# AFE.net
KiCad netlist of a schematic drawn in Altium Designer
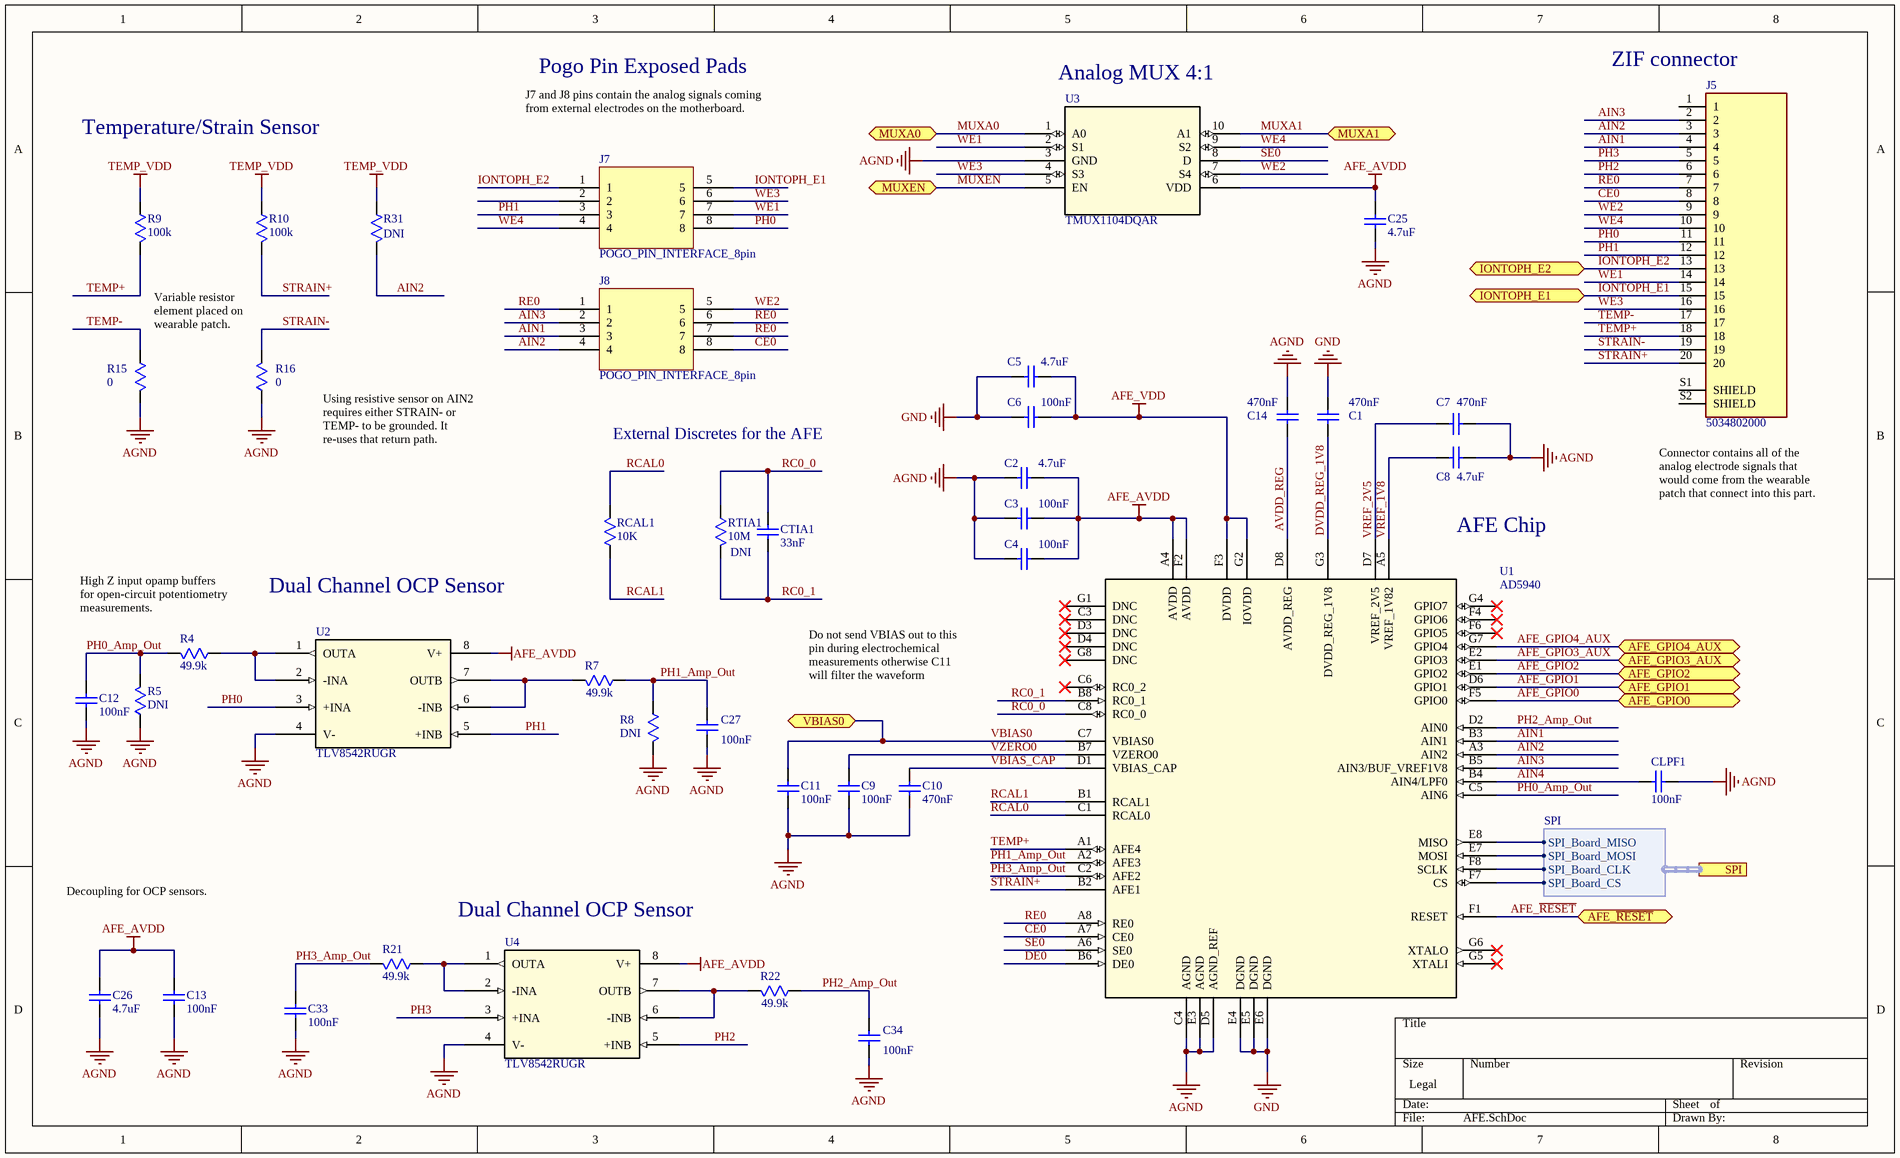
[diagram p0: AFE.SchDoc]

(export (version "E")
  (design (tool "Eeschema 10.0.6"))
  (components
    (comp (ref "C1")
      (value "470nF")
      (footprint "0201 cap")
      (description "Multilayer Chip Capacitor")
      (fields (field (name "Comment") "CAP") (field (name "DESIGNER") "OMIGA"))
      (libsource (lib "Schlib") (part "CAP SMD"))
    )
    (comp (ref "C2")
      (value "4.7uF")
      (footprint "0201 cap")
      (description "Multilayer Chip Capacitor")
      (fields (field (name "Comment") "CAP") (field (name "DESIGNER") "OMIGA"))
      (libsource (lib "Schlib") (part "CAP SMD"))
    )
    (comp (ref "C3")
      (value "100nF")
      (footprint "0201 cap")
      (description "Multilayer Chip Capacitor")
      (fields (field (name "Comment") "CAP") (field (name "DESIGNER") "OMIGA"))
      (libsource (lib "Schlib") (part "CAP SMD"))
    )
    (comp (ref "C4")
      (value "100nF")
      (footprint "0201 cap")
      (description "Multilayer Chip Capacitor")
      (fields (field (name "Comment") "CAP") (field (name "DESIGNER") "OMIGA"))
      (libsource (lib "Schlib") (part "CAP SMD"))
    )
    (comp (ref "C5")
      (value "4.7uF")
      (footprint "0201 cap")
      (description "Multilayer Chip Capacitor")
      (fields (field (name "Comment") "CAP") (field (name "DESIGNER") "OMIGA"))
      (libsource (lib "Schlib") (part "CAP SMD"))
    )
    (comp (ref "C6")
      (value "100nF")
      (footprint "0201 cap")
      (description "Multilayer Chip Capacitor")
      (fields (field (name "Comment") "CAP") (field (name "DESIGNER") "OMIGA"))
      (libsource (lib "Schlib") (part "CAP SMD"))
    )
    (comp (ref "C7")
      (value "470nF")
      (footprint "0201 cap")
      (description "Multilayer Chip Capacitor")
      (fields (field (name "Comment") "CAP") (field (name "DESIGNER") "OMIGA"))
      (libsource (lib "Schlib") (part "CAP SMD"))
    )
    (comp (ref "C8")
      (value "4.7uF")
      (footprint "0201 cap")
      (description "Multilayer Chip Capacitor")
      (fields (field (name "Comment") "CAP") (field (name "DESIGNER") "OMIGA"))
      (libsource (lib "Schlib") (part "CAP SMD"))
    )
    (comp (ref "C9")
      (value "100nF")
      (footprint "0402-CAP")
      (description "Multilayer Chip Capacitor")
      (fields (field (name "Comment") "CAP") (field (name "DESIGNER") "OMIGA"))
      (libsource (lib "Schlib") (part "CAP SMD"))
    )
    (comp (ref "C10")
      (value "470nF")
      (footprint "0201 cap")
      (description "Multilayer Chip Capacitor")
      (fields (field (name "Comment") "CAP") (field (name "DESIGNER") "OMIGA"))
      (libsource (lib "Schlib") (part "CAP SMD"))
    )
    (comp (ref "C11")
      (value "100nF")
      (footprint "0402-CAP")
      (description "Multilayer Chip Capacitor")
      (fields (field (name "Comment") "CAP") (field (name "DESIGNER") "OMIGA"))
      (libsource (lib "Schlib") (part "CAP SMD"))
    )
    (comp (ref "C12")
      (value "100nF")
      (footprint "0201 cap")
      (description "Multilayer Chip Capacitor")
      (fields (field (name "Comment") "CAP") (field (name "DESIGNER") "OMIGA"))
      (libsource (lib "Schlib") (part "CAP SMD"))
    )
    (comp (ref "C13")
      (value "100nF")
      (footprint "0201 cap")
      (description "Multilayer Chip Capacitor")
      (fields (field (name "Comment") "CAP") (field (name "DESIGNER") "OMIGA"))
      (libsource (lib "Schlib") (part "CAP SMD"))
    )
    (comp (ref "C14")
      (value "470nF")
      (footprint "0201 cap")
      (description "Multilayer Chip Capacitor")
      (fields (field (name "Comment") "CAP") (field (name "DESIGNER") "OMIGA"))
      (libsource (lib "Schlib") (part "CAP SMD"))
    )
    (comp (ref "C25")
      (value "4.7uF")
      (footprint "0201 cap")
      (description "Multilayer Chip Capacitor")
      (fields (field (name "Comment") "CAP") (field (name "DESIGNER") "OMIGA"))
      (libsource (lib "Schlib") (part "CAP SMD"))
    )
    (comp (ref "C26")
      (value "4.7uF")
      (footprint "0201 cap")
      (description "Multilayer Chip Capacitor")
      (fields (field (name "Comment") "CAP") (field (name "DESIGNER") "OMIGA"))
      (libsource (lib "Schlib") (part "CAP SMD"))
    )
    (comp (ref "C27")
      (value "100nF")
      (footprint "0201 cap")
      (description "Multilayer Chip Capacitor")
      (fields (field (name "Comment") "CAP") (field (name "DESIGNER") "OMIGA"))
      (libsource (lib "Schlib") (part "CAP SMD"))
    )
    (comp (ref "C33")
      (value "100nF")
      (footprint "0201 cap")
      (description "Multilayer Chip Capacitor")
      (fields (field (name "Comment") "CAP") (field (name "DESIGNER") "OMIGA"))
      (libsource (lib "Schlib") (part "CAP SMD"))
    )
    (comp (ref "C34")
      (value "100nF")
      (footprint "0201 cap")
      (description "Multilayer Chip Capacitor")
      (fields (field (name "Comment") "CAP") (field (name "DESIGNER") "OMIGA"))
      (libsource (lib "Schlib") (part "CAP SMD"))
    )
    (comp (ref "CLPF1")
      (value "100nF")
      (footprint "0201 cap")
      (description "Multilayer Chip Capacitor")
      (fields (field (name "Comment") "CAP") (field (name "DESIGNER") "OMIGA"))
      (libsource (lib "Schlib") (part "CAP SMD"))
    )
    (comp (ref "CTIA1")
      (value "33nF")
      (footprint "0402-CAP")
      (description "Multilayer Chip Capacitor")
      (fields (field (name "Comment") "CAP") (field (name "DESIGNER") "OMIGA"))
      (libsource (lib "Schlib") (part "CAP SMD"))
    )
    (comp (ref "J5")
      (value "5034802000")
      (footprint "MOLEX_5034802000")
      (description "20 Position FFC, FPC Connector Contacts, Top and Bottom 0.020 (0.50mm) Surface Mount, Right Angle")
      (fields (field (name "MP") "503480-2000") (field (name "MF") "Molex"))
      (libsource (lib "Schlib") (part "5034802000"))
    )
    (comp (ref "J7")
      (value "POGO_PIN_INTERFACE_8pin")
      (footprint "POGO_PIN_INTERFACE_8pin")
      (libsource (lib "Schlib") (part "POGO_PIN_INTERFACE_8pin"))
    )
    (comp (ref "J8")
      (value "POGO_PIN_INTERFACE_8pin")
      (footprint "POGO_PIN_INTERFACE_8pin")
      (libsource (lib "Schlib") (part "POGO_PIN_INTERFACE_8pin"))
    )
    (comp (ref "R4")
      (value "49.9k")
      (footprint "0201 res")
      (description "Surface Mount Resistor")
      (fields (field (name "Comment") "RES") (field (name "DESIGNER") "OMIGA"))
      (libsource (lib "Schlib") (part "RES SMD"))
    )
    (comp (ref "R5")
      (value "RES")
      (footprint "0201 res")
      (description "Surface Mount Resistor")
      (fields (field (name "DO NOT INSTALL") "DNI") (field (name "DESIGNER") "OMIGA"))
      (libsource (lib "Schlib") (part "RES SMD"))
    )
    (comp (ref "R7")
      (value "49.9k")
      (footprint "0201 res")
      (description "Surface Mount Resistor")
      (fields (field (name "Comment") "RES") (field (name "DESIGNER") "OMIGA"))
      (libsource (lib "Schlib") (part "RES SMD"))
    )
    (comp (ref "R8")
      (value "RES")
      (footprint "0201 res")
      (description "Surface Mount Resistor")
      (fields (field (name "DO NOT INSTALL") "DNI") (field (name "DESIGNER") "OMIGA"))
      (libsource (lib "Schlib") (part "RES SMD"))
    )
    (comp (ref "R9")
      (value "100k")
      (footprint "0201 res")
      (description "Surface Mount Resistor")
      (fields (field (name "Comment") "RES") (field (name "DESIGNER") "OMIGA"))
      (libsource (lib "Schlib") (part "RES SMD"))
    )
    (comp (ref "R10")
      (value "100k")
      (footprint "0201 res")
      (description "Surface Mount Resistor")
      (fields (field (name "Comment") "RES") (field (name "DESIGNER") "OMIGA"))
      (libsource (lib "Schlib") (part "RES SMD"))
    )
    (comp (ref "R15")
      (value "0")
      (footprint "0201 res")
      (description "Surface Mount Resistor")
      (fields (field (name "Comment") "RES") (field (name "DESIGNER") "OMIGA"))
      (libsource (lib "Schlib") (part "RES SMD"))
    )
    (comp (ref "R16")
      (value "0")
      (footprint "0201 res")
      (description "Surface Mount Resistor")
      (fields (field (name "Comment") "RES") (field (name "DESIGNER") "OMIGA"))
      (libsource (lib "Schlib") (part "RES SMD"))
    )
    (comp (ref "R21")
      (value "49.9k")
      (footprint "0201 res")
      (description "Surface Mount Resistor")
      (fields (field (name "Comment") "RES") (field (name "DESIGNER") "OMIGA"))
      (libsource (lib "Schlib") (part "RES SMD"))
    )
    (comp (ref "R22")
      (value "49.9k")
      (footprint "0201 res")
      (description "Surface Mount Resistor")
      (fields (field (name "Comment") "RES") (field (name "DESIGNER") "OMIGA"))
      (libsource (lib "Schlib") (part "RES SMD"))
    )
    (comp (ref "R31")
      (value "RES")
      (footprint "0201 res")
      (description "Surface Mount Resistor")
      (fields (field (name "DO NOT INSTALL") "DNI") (field (name "DESIGNER") "OMIGA"))
      (libsource (lib "Schlib") (part "RES SMD"))
    )
    (comp (ref "RCAL1")
      (value "10K")
      (footprint "0201 res")
      (description "Surface Mount Resistor")
      (fields (field (name "Comment") "RES") (field (name "DESIGNER") "OMIGA"))
      (libsource (lib "Schlib") (part "RES 0201"))
    )
    (comp (ref "RTIA1")
      (value "10M")
      (footprint "0402-RES")
      (description "Surface Mount Resistor")
      (fields
        (field (name "DO NOT INSTALL") "DNI")
        (field (name "Comment") "RES")
        (field (name "DESIGNER") "OMIGA")
      )
      (libsource (lib "Schlib") (part "RES SMD"))
    )
    (comp (ref "U1")
      (value "AD5940")
      (footprint "CB-56-3_ADI")
      (description "High Precision, Impedance, and\r\nElectrochemical Front End")
      (libsource (lib "Schlib") (part "AD5940"))
    )
    (comp (ref "U2")
      (value "TLV8542RUGR")
      (footprint "QFN50P150X150X40-8N")
      (description "Low power, tiny, low input bias current opamp")
      (libsource (lib "Schlib") (part "TLV8542RUGR"))
    )
    (comp (ref "U3")
      (value "TMUX1104DQAR")
      (footprint "USON_104DQAR_TEX")
      (description "No Description Available")
      (fields (field (name "COPYRIGHT") "Copyright (C) 2022 Ultra Librarian. All rights reserved."))
      (libsource (lib "Schlib") (part "TMUX1104DQAR_1"))
    )
    (comp (ref "U4")
      (value "TLV8542RUGR")
      (footprint "QFN50P150X150X40-8N")
      (description "Low power, tiny, low input bias current opamp")
      (libsource (lib "Schlib") (part "TLV8542RUGR"))
    )
  )
  (nets
    (net (code "2") (name "/AFE_GPIO0") (class "Default")
      (node (ref "U1") (pin "F5") (pinfunction "GPIO0_F5") (pintype "bidirectional"))
    )
    (net (code "3") (name "/AFE_GPIO1") (class "Default")
      (node (ref "U1") (pin "D6") (pinfunction "GPIO1_D6") (pintype "bidirectional"))
    )
    (net (code "4") (name "/AFE_GPIO2") (class "Default")
      (node (ref "U1") (pin "E1") (pinfunction "GPIO2_E1") (pintype "bidirectional"))
    )
    (net (code "5") (name "/AFE_GPIO3_AUX") (class "Default")
      (node (ref "U1") (pin "E2") (pinfunction "GPIO3_E2") (pintype "bidirectional"))
    )
    (net (code "6") (name "/AFE_GPIO4_AUX") (class "Default")
      (node (ref "U1") (pin "G7") (pinfunction "GPIO4_G7") (pintype "bidirectional"))
    )
    (net (code "7") (name "/AFE_~{RESET}") (class "Default")
      (node (ref "U1") (pin "F1") (pinfunction "RESET_F1") (pintype "input"))
    )
    (net (code "8") (name "/AIN1") (class "Default")
      (node (ref "J5") (pin "4") (pinfunction "4_4") (pintype "passive"))
      (node (ref "J8") (pin "3") (pinfunction "3_3") (pintype "passive"))
      (node (ref "U1") (pin "B3") (pinfunction "AIN1_B3") (pintype "input"))
    )
    (net (code "9") (name "/AIN2") (class "Default")
      (node (ref "J5") (pin "3") (pinfunction "3_3") (pintype "passive"))
      (node (ref "J8") (pin "4") (pinfunction "4_4") (pintype "passive"))
      (node (ref "R31") (pin "2") (pinfunction "2_2") (pintype "passive"))
      (node (ref "U1") (pin "A3") (pinfunction "AIN2_A3") (pintype "input"))
    )
    (net (code "10") (name "/AIN3") (class "Default")
      (node (ref "J5") (pin "2") (pinfunction "2_2") (pintype "passive"))
      (node (ref "J8") (pin "2") (pinfunction "2_2") (pintype "passive"))
      (node (ref "U1") (pin "B5") (pinfunction "AIN3/BUF_VREF1V8_B5") (pintype "input"))
    )
    (net (code "11") (name "/AIN4") (class "Default")
      (node (ref "CLPF1") (pin "1") (pinfunction "1_1") (pintype "passive"))
      (node (ref "U1") (pin "B4") (pinfunction "AIN4/LPF0_B4") (pintype "input"))
    )
    (net (code "12") (name "/AVDD_REG") (class "Default")
      (node (ref "C14") (pin "2") (pinfunction "2_2") (pintype "passive"))
      (node (ref "U1") (pin "D8") (pinfunction "AVDD_REG_D8") (pintype "power_in"))
    )
    (net (code "13") (name "/CE0") (class "Default")
      (node (ref "J5") (pin "8") (pinfunction "8_8") (pintype "passive"))
      (node (ref "J8") (pin "8") (pinfunction "8_8") (pintype "passive"))
      (node (ref "U1") (pin "A7") (pinfunction "CE0_A7") (pintype "input"))
    )
    (net (code "14") (name "/DE0") (class "Default")
      (node (ref "U1") (pin "B6") (pinfunction "DE0_B6") (pintype "input"))
    )
    (net (code "15") (name "/DVDD_REG_1V8") (class "Default")
      (node (ref "C1") (pin "2") (pinfunction "2_2") (pintype "passive"))
      (node (ref "U1") (pin "G3") (pinfunction "DVDD_REG_1V8_G3") (pintype "power_in"))
    )
    (net (code "16") (name "/IONTOPH_E1") (class "Default")
      (node (ref "J5") (pin "15") (pinfunction "15_15") (pintype "passive"))
      (node (ref "J7") (pin "5") (pinfunction "5_5") (pintype "passive"))
    )
    (net (code "17") (name "/IONTOPH_E2") (class "Default")
      (node (ref "J5") (pin "13") (pinfunction "13_13") (pintype "passive"))
      (node (ref "J7") (pin "1") (pinfunction "1_1") (pintype "passive"))
    )
    (net (code "18") (name "/MUXA0") (class "Default")
      (node (ref "U3") (pin "1") (pinfunction "A0_1") (pintype "bidirectional"))
    )
    (net (code "19") (name "/MUXA1") (class "Default")
      (node (ref "U3") (pin "10") (pinfunction "A1_10") (pintype "bidirectional"))
    )
    (net (code "20") (name "/MUXEN") (class "Default")
      (node (ref "U3") (pin "5") (pinfunction "EN_5") (pintype "passive"))
    )
    (net (code "21") (name "/PH0") (class "Default")
      (node (ref "J5") (pin "11") (pinfunction "11_11") (pintype "passive"))
      (node (ref "J7") (pin "8") (pinfunction "8_8") (pintype "passive"))
      (node (ref "U2") (pin "3") (pinfunction "+INA_3") (pintype "input"))
    )
    (net (code "22") (name "/PH0_Amp_Out") (class "Default")
      (node (ref "C12") (pin "1") (pinfunction "1_1") (pintype "passive"))
      (node (ref "R4") (pin "1") (pinfunction "1_1") (pintype "passive"))
      (node (ref "R5") (pin "1") (pinfunction "1_1") (pintype "passive"))
      (node (ref "U1") (pin "C5") (pinfunction "AIN6_C5") (pintype "input"))
    )
    (net (code "23") (name "/PH1") (class "Default")
      (node (ref "J5") (pin "12") (pinfunction "12_12") (pintype "passive"))
      (node (ref "J7") (pin "3") (pinfunction "3_3") (pintype "passive"))
      (node (ref "U2") (pin "5") (pinfunction "+INB_5") (pintype "input"))
    )
    (net (code "24") (name "/PH1_Amp_Out") (class "Default")
      (node (ref "C27") (pin "1") (pinfunction "1_1") (pintype "passive"))
      (node (ref "R7") (pin "1") (pinfunction "1_1") (pintype "passive"))
      (node (ref "R8") (pin "1") (pinfunction "1_1") (pintype "passive"))
      (node (ref "U1") (pin "A2") (pinfunction "AFE3_A2") (pintype "bidirectional"))
    )
    (net (code "25") (name "/PH2") (class "Default")
      (node (ref "J5") (pin "6") (pinfunction "6_6") (pintype "passive"))
      (node (ref "U4") (pin "5") (pinfunction "+INB_5") (pintype "input"))
    )
    (net (code "26") (name "/PH2_Amp_Out") (class "Default")
      (node (ref "C34") (pin "1") (pinfunction "1_1") (pintype "passive"))
      (node (ref "R22") (pin "1") (pinfunction "1_1") (pintype "passive"))
      (node (ref "U1") (pin "D2") (pinfunction "AIN0_D2") (pintype "input"))
    )
    (net (code "27") (name "/PH3") (class "Default")
      (node (ref "J5") (pin "5") (pinfunction "5_5") (pintype "passive"))
      (node (ref "U4") (pin "3") (pinfunction "+INA_3") (pintype "input"))
    )
    (net (code "28") (name "/PH3_Amp_Out") (class "Default")
      (node (ref "C33") (pin "1") (pinfunction "1_1") (pintype "passive"))
      (node (ref "R21") (pin "1") (pinfunction "1_1") (pintype "passive"))
      (node (ref "U1") (pin "C2") (pinfunction "AFE2_C2") (pintype "bidirectional"))
    )
    (net (code "29") (name "/RC0_0") (class "Default")
      (node (ref "CTIA1") (pin "1") (pinfunction "1_1") (pintype "passive"))
      (node (ref "RTIA1") (pin "1") (pinfunction "1_1") (pintype "passive"))
      (node (ref "U1") (pin "C8") (pinfunction "RC0_0_C8") (pintype "bidirectional"))
    )
    (net (code "30") (name "/RC0_1") (class "Default")
      (node (ref "CTIA1") (pin "2") (pinfunction "2_2") (pintype "passive"))
      (node (ref "RTIA1") (pin "2") (pinfunction "2_2") (pintype "passive"))
      (node (ref "U1") (pin "B8") (pinfunction "RC0_1_B8") (pintype "input"))
    )
    (net (code "31") (name "/RCAL0") (class "Default")
      (node (ref "RCAL1") (pin "2") (pinfunction "2_2") (pintype "passive"))
      (node (ref "U1") (pin "C1") (pinfunction "RCAL0_C1") (pintype "passive"))
    )
    (net (code "32") (name "/RCAL1") (class "Default")
      (node (ref "RCAL1") (pin "1") (pinfunction "1_1") (pintype "passive"))
      (node (ref "U1") (pin "B1") (pinfunction "RCAL1_B1") (pintype "passive"))
    )
    (net (code "33") (name "/RE0") (class "Default")
      (node (ref "J5") (pin "7") (pinfunction "7_7") (pintype "passive"))
      (node (ref "J8") (pin "1") (pinfunction "1_1") (pintype "passive"))
      (node (ref "J8") (pin "6") (pinfunction "6_6") (pintype "passive"))
      (node (ref "J8") (pin "7") (pinfunction "7_7") (pintype "passive"))
      (node (ref "U1") (pin "A8") (pinfunction "RE0_A8") (pintype "input"))
    )
    (net (code "34") (name "/SE0") (class "Default")
      (node (ref "U1") (pin "A6") (pinfunction "SE0_A6") (pintype "input"))
      (node (ref "U3") (pin "8") (pinfunction "D_8") (pintype "passive"))
    )
    (net (code "35") (name "/SPI_Board_CLK") (class "Default")
      (node (ref "U1") (pin "F8") (pinfunction "SCLK_F8") (pintype "input"))
    )
    (net (code "36") (name "/SPI_Board_CS") (class "Default")
      (node (ref "U1") (pin "F7") (pinfunction "CS_F7") (pintype "bidirectional"))
    )
    (net (code "37") (name "/SPI_Board_MISO") (class "Default")
      (node (ref "U1") (pin "E8") (pinfunction "MISO_E8") (pintype "output"))
    )
    (net (code "38") (name "/SPI_Board_MOSI") (class "Default")
      (node (ref "U1") (pin "E7") (pinfunction "MOSI_E7") (pintype "input"))
    )
    (net (code "39") (name "/STRAIN+") (class "Default")
      (node (ref "J5") (pin "20") (pinfunction "20_20") (pintype "passive"))
      (node (ref "R10") (pin "2") (pinfunction "2_2") (pintype "passive"))
      (node (ref "U1") (pin "B2") (pinfunction "AFE1_B2") (pintype "passive"))
    )
    (net (code "40") (name "/STRAIN-") (class "Default")
      (node (ref "J5") (pin "19") (pinfunction "19_19") (pintype "passive"))
      (node (ref "R16") (pin "1") (pinfunction "1_1") (pintype "passive"))
    )
    (net (code "41") (name "/TEMP+") (class "Default")
      (node (ref "J5") (pin "18") (pinfunction "18_18") (pintype "passive"))
      (node (ref "R9") (pin "2") (pinfunction "2_2") (pintype "passive"))
      (node (ref "U1") (pin "A1") (pinfunction "AFE4_A1") (pintype "bidirectional"))
    )
    (net (code "42") (name "/TEMP-") (class "Default")
      (node (ref "J5") (pin "17") (pinfunction "17_17") (pintype "passive"))
      (node (ref "R15") (pin "1") (pinfunction "1_1") (pintype "passive"))
    )
    (net (code "43") (name "/VBIAS0") (class "Default")
      (node (ref "C11") (pin "2") (pinfunction "2_2") (pintype "passive"))
      (node (ref "U1") (pin "C7") (pinfunction "VBIAS0_C7") (pintype "passive"))
    )
    (net (code "44") (name "/VBIAS_CAP") (class "Default")
      (node (ref "C10") (pin "2") (pinfunction "2_2") (pintype "passive"))
      (node (ref "U1") (pin "D1") (pinfunction "VBIAS_CAP_D1") (pintype "power_in"))
    )
    (net (code "45") (name "/VREF_1V8") (class "Default")
      (node (ref "C8") (pin "2") (pinfunction "2_2") (pintype "passive"))
      (node (ref "U1") (pin "A5") (pinfunction "VREF_1V82_A5") (pintype "power_in"))
    )
    (net (code "46") (name "/VREF_2V5") (class "Default")
      (node (ref "C7") (pin "2") (pinfunction "2_2") (pintype "passive"))
      (node (ref "U1") (pin "D7") (pinfunction "VREF_2V5_D7") (pintype "power_in"))
    )
    (net (code "47") (name "/VZERO0") (class "Default")
      (node (ref "C9") (pin "2") (pinfunction "2_2") (pintype "passive"))
      (node (ref "U1") (pin "B7") (pinfunction "VZERO0_B7") (pintype "power_in"))
    )
    (net (code "48") (name "/WE1") (class "Default")
      (node (ref "J5") (pin "14") (pinfunction "14_14") (pintype "passive"))
      (node (ref "J7") (pin "7") (pinfunction "7_7") (pintype "passive"))
      (node (ref "U3") (pin "2") (pinfunction "S1_2") (pintype "bidirectional"))
    )
    (net (code "49") (name "/WE2") (class "Default")
      (node (ref "J5") (pin "9") (pinfunction "9_9") (pintype "passive"))
      (node (ref "J8") (pin "5") (pinfunction "5_5") (pintype "passive"))
      (node (ref "U3") (pin "7") (pinfunction "S4_7") (pintype "bidirectional"))
    )
    (net (code "50") (name "/WE3") (class "Default")
      (node (ref "J5") (pin "16") (pinfunction "16_16") (pintype "passive"))
      (node (ref "J7") (pin "6") (pinfunction "6_6") (pintype "passive"))
      (node (ref "U3") (pin "4") (pinfunction "S3_4") (pintype "bidirectional"))
    )
    (net (code "51") (name "/WE4") (class "Default")
      (node (ref "J5") (pin "10") (pinfunction "10_10") (pintype "passive"))
      (node (ref "J7") (pin "4") (pinfunction "4_4") (pintype "passive"))
      (node (ref "U3") (pin "9") (pinfunction "S2_9") (pintype "bidirectional"))
    )
    (net (code "53") (name "AFE_AVDD") (class "Default")
      (node (ref "C13") (pin "2") (pinfunction "2_2") (pintype "passive"))
      (node (ref "C2") (pin "1") (pinfunction "1_1") (pintype "passive"))
      (node (ref "C25") (pin "2") (pinfunction "2_2") (pintype "passive"))
      (node (ref "C26") (pin "2") (pinfunction "2_2") (pintype "passive"))
      (node (ref "C3") (pin "1") (pinfunction "1_1") (pintype "passive"))
      (node (ref "C4") (pin "1") (pinfunction "1_1") (pintype "passive"))
      (node (ref "U1") (pin "A4") (pinfunction "AVDD_A4") (pintype "power_in"))
      (node (ref "U1") (pin "F2") (pinfunction "AVDD_F2") (pintype "power_in"))
      (node (ref "U2") (pin "8") (pinfunction "V+_8") (pintype "power_in"))
      (node (ref "U3") (pin "6") (pinfunction "VDD_6") (pintype "power_in"))
      (node (ref "U4") (pin "8") (pinfunction "V+_8") (pintype "power_in"))
    )
    (net (code "54") (name "AFE_VDD") (class "Default")
      (node (ref "C5") (pin "1") (pinfunction "1_1") (pintype "passive"))
      (node (ref "C6") (pin "1") (pinfunction "1_1") (pintype "passive"))
      (node (ref "U1") (pin "F3") (pinfunction "DVDD_F3") (pintype "power_in"))
      (node (ref "U1") (pin "G2") (pinfunction "IOVDD_G2") (pintype "power_in"))
    )
    (net (code "55") (name "AGND") (class "Default")
      (node (ref "C10") (pin "1") (pinfunction "1_1") (pintype "passive"))
      (node (ref "C11") (pin "1") (pinfunction "1_1") (pintype "passive"))
      (node (ref "C12") (pin "2") (pinfunction "2_2") (pintype "passive"))
      (node (ref "C13") (pin "1") (pinfunction "1_1") (pintype "passive"))
      (node (ref "C14") (pin "1") (pinfunction "1_1") (pintype "passive"))
      (node (ref "C2") (pin "2") (pinfunction "2_2") (pintype "passive"))
      (node (ref "C25") (pin "1") (pinfunction "1_1") (pintype "passive"))
      (node (ref "C26") (pin "1") (pinfunction "1_1") (pintype "passive"))
      (node (ref "C27") (pin "2") (pinfunction "2_2") (pintype "passive"))
      (node (ref "C3") (pin "2") (pinfunction "2_2") (pintype "passive"))
      (node (ref "C33") (pin "2") (pinfunction "2_2") (pintype "passive"))
      (node (ref "C34") (pin "2") (pinfunction "2_2") (pintype "passive"))
      (node (ref "C4") (pin "2") (pinfunction "2_2") (pintype "passive"))
      (node (ref "C7") (pin "1") (pinfunction "1_1") (pintype "passive"))
      (node (ref "C8") (pin "1") (pinfunction "1_1") (pintype "passive"))
      (node (ref "C9") (pin "1") (pinfunction "1_1") (pintype "passive"))
      (node (ref "CLPF1") (pin "2") (pinfunction "2_2") (pintype "passive"))
      (node (ref "R15") (pin "2") (pinfunction "2_2") (pintype "passive"))
      (node (ref "R16") (pin "2") (pinfunction "2_2") (pintype "passive"))
      (node (ref "R5") (pin "2") (pinfunction "2_2") (pintype "passive"))
      (node (ref "R8") (pin "2") (pinfunction "2_2") (pintype "passive"))
      (node (ref "U1") (pin "C4") (pinfunction "AGND_C4") (pintype "passive"))
      (node (ref "U1") (pin "D5") (pinfunction "AGND_REF_D5") (pintype "passive"))
      (node (ref "U1") (pin "E3") (pinfunction "AGND_E3") (pintype "passive"))
      (node (ref "U2") (pin "4") (pinfunction "V-_4") (pintype "power_in"))
      (node (ref "U3") (pin "3") (pinfunction "GND_3") (pintype "passive"))
      (node (ref "U4") (pin "4") (pinfunction "V-_4") (pintype "power_in"))
    )
    (net (code "56") (name "GND") (class "Default")
      (node (ref "C1") (pin "1") (pinfunction "1_1") (pintype "passive"))
      (node (ref "C5") (pin "2") (pinfunction "2_2") (pintype "passive"))
      (node (ref "C6") (pin "2") (pinfunction "2_2") (pintype "passive"))
      (node (ref "U1") (pin "E4") (pinfunction "DGND_E4") (pintype "passive"))
      (node (ref "U1") (pin "E5") (pinfunction "DGND_E5") (pintype "passive"))
      (node (ref "U1") (pin "E6") (pinfunction "DGND_E6") (pintype "passive"))
    )
    (net (code "57") (name "Net-(U2--INA)") (class "Default")
      (node (ref "R4") (pin "2") (pinfunction "2_2") (pintype "passive"))
      (node (ref "U2") (pin "1") (pinfunction "OUTA_1") (pintype "output"))
      (node (ref "U2") (pin "2") (pinfunction "-INA_2") (pintype "input"))
    )
    (net (code "58") (name "Net-(U2--INB)") (class "Default")
      (node (ref "R7") (pin "2") (pinfunction "2_2") (pintype "passive"))
      (node (ref "U2") (pin "6") (pinfunction "-INB_6") (pintype "input"))
      (node (ref "U2") (pin "7") (pinfunction "OUTB_7") (pintype "output"))
    )
    (net (code "59") (name "Net-(U4--INA)") (class "Default")
      (node (ref "R21") (pin "2") (pinfunction "2_2") (pintype "passive"))
      (node (ref "U4") (pin "1") (pinfunction "OUTA_1") (pintype "output"))
      (node (ref "U4") (pin "2") (pinfunction "-INA_2") (pintype "input"))
    )
    (net (code "60") (name "Net-(U4--INB)") (class "Default")
      (node (ref "R22") (pin "2") (pinfunction "2_2") (pintype "passive"))
      (node (ref "U4") (pin "6") (pinfunction "-INB_6") (pintype "input"))
      (node (ref "U4") (pin "7") (pinfunction "OUTB_7") (pintype "output"))
    )
    (net (code "61") (name "TEMP_VDD") (class "Default")
      (node (ref "R10") (pin "1") (pinfunction "1_1") (pintype "passive"))
      (node (ref "R31") (pin "1") (pinfunction "1_1") (pintype "passive"))
      (node (ref "R9") (pin "1") (pinfunction "1_1") (pintype "passive"))
    )
    (net (code "62") (name "unconnected-(J5-Pad1)") (class "Default")
      (node (ref "J5") (pin "1") (pinfunction "1_1") (pintype "passive"))
    )
    (net (code "63") (name "unconnected-(J5-SHIELD-PadS1)") (class "Default")
      (node (ref "J5") (pin "S1") (pinfunction "SHIELD_S1") (pintype "passive"))
    )
    (net (code "64") (name "unconnected-(J5-SHIELD-PadS2)") (class "Default")
      (node (ref "J5") (pin "S2") (pinfunction "SHIELD_S2") (pintype "passive"))
    )
    (net (code "65") (name "unconnected-(J7-Pad2)") (class "Default")
      (node (ref "J7") (pin "2") (pinfunction "2_2") (pintype "passive"))
    )
    (net (code "66") (name "unconnected-(U1-DNC-PadC3)") (class "Default")
      (node (ref "U1") (pin "C3") (pinfunction "DNC_C3") (pintype "passive+no_connect"))
    )
    (net (code "67") (name "unconnected-(U1-DNC-PadD3)") (class "Default")
      (node (ref "U1") (pin "D3") (pinfunction "DNC_D3") (pintype "passive+no_connect"))
    )
    (net (code "68") (name "unconnected-(U1-DNC-PadD4)") (class "Default")
      (node (ref "U1") (pin "D4") (pinfunction "DNC_D4") (pintype "passive+no_connect"))
    )
    (net (code "69") (name "unconnected-(U1-DNC-PadG1)") (class "Default")
      (node (ref "U1") (pin "G1") (pinfunction "DNC_G1") (pintype "passive+no_connect"))
    )
    (net (code "70") (name "unconnected-(U1-DNC-PadG8)") (class "Default")
      (node (ref "U1") (pin "G8") (pinfunction "DNC_G8") (pintype "passive+no_connect"))
    )
    (net (code "71") (name "unconnected-(U1-GPIO5-PadF6)") (class "Default")
      (node (ref "U1") (pin "F6") (pinfunction "GPIO5_F6") (pintype "bidirectional+no_connect"))
    )
    (net (code "72") (name "unconnected-(U1-GPIO6-PadF4)") (class "Default")
      (node (ref "U1") (pin "F4") (pinfunction "GPIO6_F4") (pintype "bidirectional+no_connect"))
    )
    (net (code "73") (name "unconnected-(U1-GPIO7-PadG4)") (class "Default")
      (node (ref "U1") (pin "G4") (pinfunction "GPIO7_G4") (pintype "bidirectional+no_connect"))
    )
    (net (code "74") (name "unconnected-(U1-RC0_2-PadC6)") (class "Default")
      (node (ref "U1") (pin "C6") (pinfunction "RC0_2_C6") (pintype "bidirectional+no_connect"))
    )
    (net (code "75") (name "unconnected-(U1-XTALI-PadG5)") (class "Default")
      (node (ref "U1") (pin "G5") (pinfunction "XTALI_G5") (pintype "input+no_connect"))
    )
    (net (code "76") (name "unconnected-(U1-XTALO-PadG6)") (class "Default")
      (node (ref "U1") (pin "G6") (pinfunction "XTALO_G6") (pintype "output+no_connect"))
    )
  )
)
